# W011X.net
KiCad netlist of a schematic drawn in EAGLE
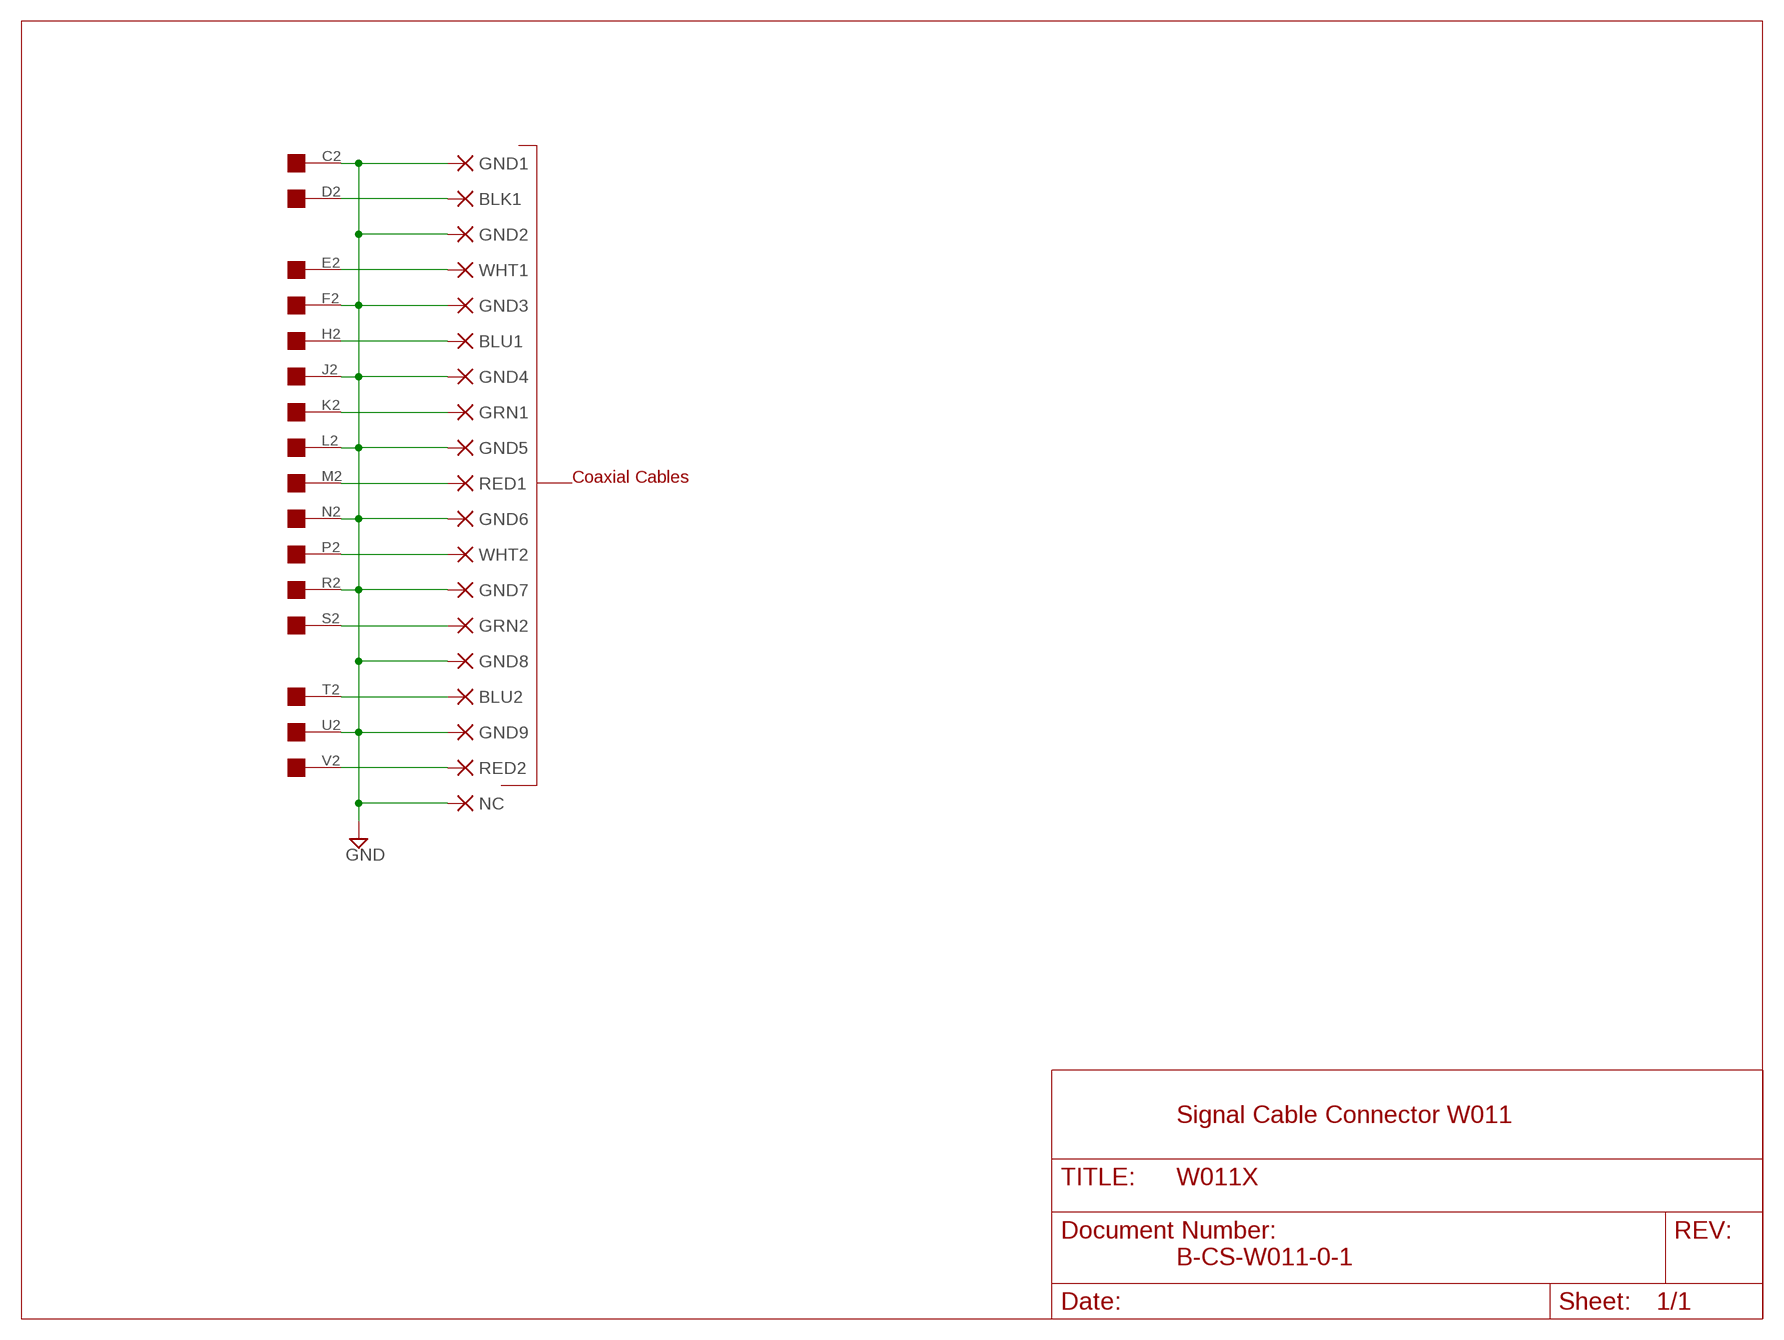
[diagram p0: schematic, sheet 1]

(export (version "E")
  (design (tool "Eeschema 10.0.6"))
  (components
    (comp (ref "BLK1")
      (value "PAD-0465")
      (footprint "eagle-import:0465")
      (libsource (lib "eagle-import") (part "PAD-0465"))
    )
    (comp (ref "BLU1")
      (value "PAD-0465")
      (footprint "eagle-import:0465")
      (libsource (lib "eagle-import") (part "PAD-0465"))
    )
    (comp (ref "BLU2")
      (value "PAD-0465")
      (footprint "eagle-import:0465")
      (libsource (lib "eagle-import") (part "PAD-0465"))
    )
    (comp (ref "GND1")
      (value "PAD-0465")
      (footprint "eagle-import:0465")
      (libsource (lib "eagle-import") (part "PAD-0465"))
    )
    (comp (ref "GND2")
      (value "PAD-0465")
      (footprint "eagle-import:0465")
      (libsource (lib "eagle-import") (part "PAD-0465"))
    )
    (comp (ref "GND3")
      (value "PAD-0465")
      (footprint "eagle-import:0465")
      (libsource (lib "eagle-import") (part "PAD-0465"))
    )
    (comp (ref "GND4")
      (value "PAD-0465")
      (footprint "eagle-import:0465")
      (libsource (lib "eagle-import") (part "PAD-0465"))
    )
    (comp (ref "GND5")
      (value "PAD-0465")
      (footprint "eagle-import:0465")
      (libsource (lib "eagle-import") (part "PAD-0465"))
    )
    (comp (ref "GND6")
      (value "PAD-0465")
      (footprint "eagle-import:0465")
      (libsource (lib "eagle-import") (part "PAD-0465"))
    )
    (comp (ref "GND7")
      (value "PAD-0465")
      (footprint "eagle-import:0465")
      (libsource (lib "eagle-import") (part "PAD-0465"))
    )
    (comp (ref "GND8")
      (value "PAD-0465")
      (footprint "eagle-import:0465")
      (libsource (lib "eagle-import") (part "PAD-0465"))
    )
    (comp (ref "GND9")
      (value "PAD-0465")
      (footprint "eagle-import:0465")
      (libsource (lib "eagle-import") (part "PAD-0465"))
    )
    (comp (ref "GRN1")
      (value "PAD-0465")
      (footprint "eagle-import:0465")
      (libsource (lib "eagle-import") (part "PAD-0465"))
    )
    (comp (ref "GRN2")
      (value "PAD-0465")
      (footprint "eagle-import:0465")
      (libsource (lib "eagle-import") (part "PAD-0465"))
    )
    (comp (ref "NC")
      (value "PAD-0465")
      (footprint "eagle-import:0465")
      (libsource (lib "eagle-import") (part "PAD-0465"))
    )
    (comp (ref "RED1")
      (value "PAD-0465")
      (footprint "eagle-import:0465")
      (libsource (lib "eagle-import") (part "PAD-0465"))
    )
    (comp (ref "RED2")
      (value "PAD-0465")
      (footprint "eagle-import:0465")
      (libsource (lib "eagle-import") (part "PAD-0465"))
    )
    (comp (ref "U$2")
      (value "EDGE-1")
      (footprint "eagle-import:EDGE-CON1")
      (libsource (lib "eagle-import") (part "EDGE-1"))
    )
    (comp (ref "WHT1")
      (value "PAD-0465")
      (footprint "eagle-import:0465")
      (libsource (lib "eagle-import") (part "PAD-0465"))
    )
    (comp (ref "WHT2")
      (value "PAD-0465")
      (footprint "eagle-import:0465")
      (libsource (lib "eagle-import") (part "PAD-0465"))
    )
  )
  (nets
    (net (code "1") (name "GND") (class "Default")
      (node (ref "GND1") (pin "P$1") (pinfunction "P_P$1") (pintype "passive"))
      (node (ref "GND2") (pin "P$1") (pinfunction "P_P$1") (pintype "passive"))
      (node (ref "GND3") (pin "P$1") (pinfunction "P_P$1") (pintype "passive"))
      (node (ref "GND4") (pin "P$1") (pinfunction "P_P$1") (pintype "passive"))
      (node (ref "GND5") (pin "P$1") (pinfunction "P_P$1") (pintype "passive"))
      (node (ref "GND6") (pin "P$1") (pinfunction "P_P$1") (pintype "passive"))
      (node (ref "GND7") (pin "P$1") (pinfunction "P_P$1") (pintype "passive"))
      (node (ref "GND8") (pin "P$1") (pinfunction "P_P$1") (pintype "passive"))
      (node (ref "GND9") (pin "P$1") (pinfunction "P_P$1") (pintype "passive"))
      (node (ref "NC") (pin "P$1") (pinfunction "P_P$1") (pintype "passive"))
      (node (ref "U$2") (pin "C2") (pinfunction "1_C2") (pintype "bidirectional"))
      (node (ref "U$2") (pin "F2") (pinfunction "1_F2") (pintype "bidirectional"))
      (node (ref "U$2") (pin "J2") (pinfunction "1_J2") (pintype "bidirectional"))
      (node (ref "U$2") (pin "L2") (pinfunction "1_L2") (pintype "bidirectional"))
      (node (ref "U$2") (pin "N2") (pinfunction "1_N2") (pintype "bidirectional"))
      (node (ref "U$2") (pin "R2") (pinfunction "1_R2") (pintype "bidirectional"))
      (node (ref "U$2") (pin "U2") (pinfunction "1_U2") (pintype "bidirectional"))
    )
    (net (code "2") (name "Net-(BLK1-P)") (class "Default")
      (node (ref "BLK1") (pin "P$1") (pinfunction "P_P$1") (pintype "passive"))
      (node (ref "U$2") (pin "D2") (pinfunction "1_D2") (pintype "bidirectional"))
    )
    (net (code "3") (name "Net-(BLU1-P)") (class "Default")
      (node (ref "BLU1") (pin "P$1") (pinfunction "P_P$1") (pintype "passive"))
      (node (ref "U$2") (pin "H2") (pinfunction "1_H2") (pintype "bidirectional"))
    )
    (net (code "4") (name "Net-(BLU2-P)") (class "Default")
      (node (ref "BLU2") (pin "P$1") (pinfunction "P_P$1") (pintype "passive"))
      (node (ref "U$2") (pin "T2") (pinfunction "1_T2") (pintype "bidirectional"))
    )
    (net (code "5") (name "Net-(GRN1-P)") (class "Default")
      (node (ref "GRN1") (pin "P$1") (pinfunction "P_P$1") (pintype "passive"))
      (node (ref "U$2") (pin "K2") (pinfunction "1_K2") (pintype "bidirectional"))
    )
    (net (code "6") (name "Net-(GRN2-P)") (class "Default")
      (node (ref "GRN2") (pin "P$1") (pinfunction "P_P$1") (pintype "passive"))
      (node (ref "U$2") (pin "S2") (pinfunction "1_S2") (pintype "bidirectional"))
    )
    (net (code "7") (name "Net-(RED1-P)") (class "Default")
      (node (ref "RED1") (pin "P$1") (pinfunction "P_P$1") (pintype "passive"))
      (node (ref "U$2") (pin "M2") (pinfunction "1_M2") (pintype "bidirectional"))
    )
    (net (code "8") (name "Net-(RED2-P)") (class "Default")
      (node (ref "RED2") (pin "P$1") (pinfunction "P_P$1") (pintype "passive"))
      (node (ref "U$2") (pin "V2") (pinfunction "1_V2") (pintype "bidirectional"))
    )
    (net (code "9") (name "Net-(U$2E-1)") (class "Default")
      (node (ref "U$2") (pin "E2") (pinfunction "1_E2") (pintype "bidirectional"))
      (node (ref "WHT1") (pin "P$1") (pinfunction "P_P$1") (pintype "passive"))
    )
    (net (code "10") (name "Net-(U$2M-1)") (class "Default")
      (node (ref "U$2") (pin "P2") (pinfunction "1_P2") (pintype "bidirectional"))
      (node (ref "WHT2") (pin "P$1") (pinfunction "P_P$1") (pintype "passive"))
    )
  )
)
